# 70.net
KiCad netlist of a schematic drawn in Altium Designer
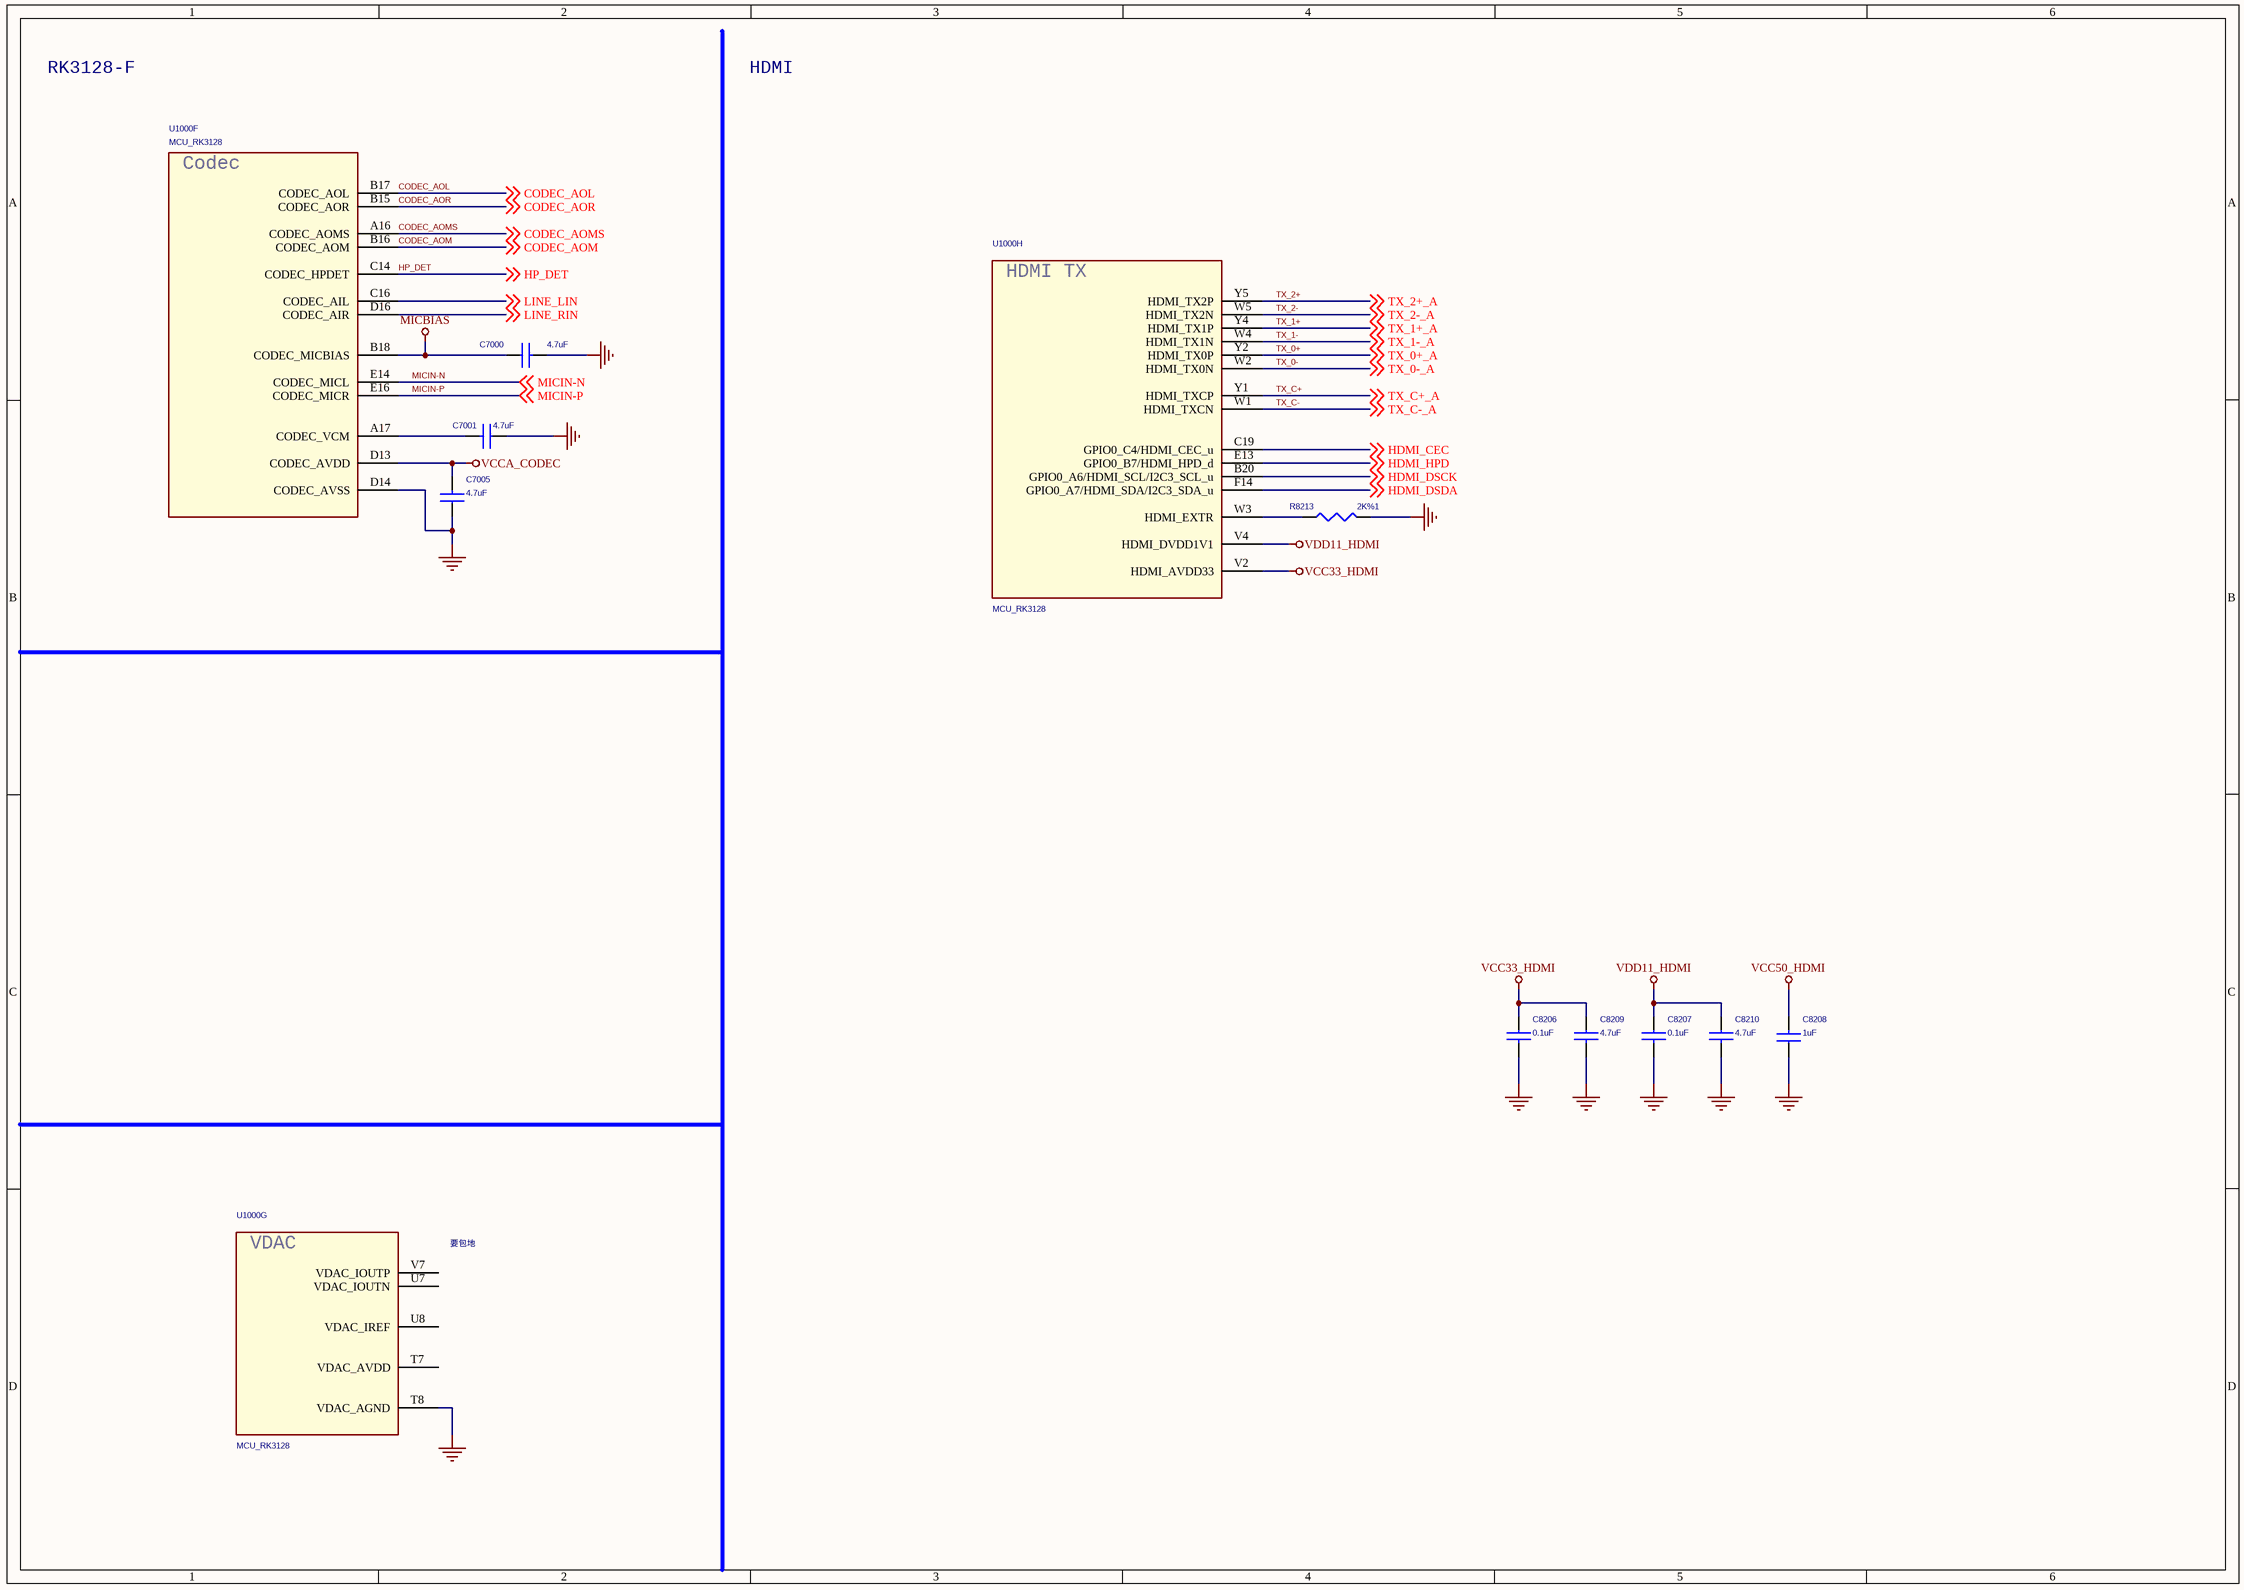
[diagram p0: 70.SchDoc]

(export (version "E")
  (design (tool "Eeschema 10.0.6"))
  (components
    (comp (ref "C7000") (value "4.7uF") (footprint "C0402") (libsource (lib "*") (part "CAP NP")))
    (comp (ref "C7001")
      (value "4.7uF")
      (footprint "C0402")
      (description "CAP,MLCC,10uF,+/-10%,X5R,16V,SMD0805")
      (libsource (lib "*") (part "CAP NP"))
    )
    (comp (ref "C7005")
      (value "4.7uF")
      (footprint "C0402")
      (description "RoHS CHIP CAP 0.1uF +10/-10% X7R")
      (libsource (lib "*") (part "CAP NP"))
    )
    (comp (ref "C8206") (value "0.1uF") (footprint "C0402") (libsource (lib "*") (part "CAP NP")))
    (comp (ref "C8207") (value "0.1uF") (footprint "C0402") (libsource (lib "*") (part "CAP NP")))
    (comp (ref "C8208")
      (value "1uF")
      (footprint "C0402")
      (description "RoHS CHIP CAP 1uF +10/-10% X5R")
      (libsource (lib "*") (part "CAP NP"))
    )
    (comp (ref "C8209") (value "4.7uF") (footprint "C0402") (libsource (lib "*") (part "CAP NP")))
    (comp (ref "C8210") (value "4.7uF") (footprint "C0402") (libsource (lib "*") (part "CAP NP")))
    (comp (ref "R8213")
      (value "2K%1")
      (footprint "R0402")
      (description "RES,thick film,3.5KOhm,+/-5%,1/16W,SMD0402")
      (libsource (lib "*") (part "RESISTOR_0"))
    )
    (comp (ref "U1000")
      (value "MCU_RK3128")
      (footprint "BGA316-14X14-0.65")
      (libsource (lib "*") (part "MCU_RK3128"))
    )
  )
  (nets
    (net (code "1") (name "CODEC_AOL") (class "Default")
      (node (ref "U1000") (pin "B17") (pinfunction "CODEC_AOL_B17") (pintype "passive"))
    )
    (net (code "2") (name "CODEC_AOM") (class "Default")
      (node (ref "U1000") (pin "B16") (pinfunction "CODEC_AOM_B16") (pintype "passive"))
    )
    (net (code "3") (name "CODEC_AOMS") (class "Default")
      (node (ref "U1000") (pin "A16") (pinfunction "CODEC_AOMS_A16") (pintype "passive"))
    )
    (net (code "4") (name "CODEC_AOR") (class "Default")
      (node (ref "U1000") (pin "B15") (pinfunction "CODEC_AOR_B15") (pintype "passive"))
    )
    (net (code "5") (name "GND") (class "Default")
      (node (ref "C7000") (pin "2") (pinfunction "2_2") (pintype "passive"))
      (node (ref "C7001") (pin "1") (pinfunction "1_1") (pintype "passive"))
      (node (ref "C7005") (pin "1") (pinfunction "1_1") (pintype "passive"))
      (node (ref "C8206") (pin "2") (pinfunction "2_2") (pintype "passive"))
      (node (ref "C8207") (pin "2") (pinfunction "2_2") (pintype "passive"))
      (node (ref "C8208") (pin "1") (pinfunction "1_1") (pintype "passive"))
      (node (ref "C8209") (pin "2") (pinfunction "2_2") (pintype "passive"))
      (node (ref "C8210") (pin "2") (pinfunction "2_2") (pintype "passive"))
      (node (ref "R8213") (pin "1") (pinfunction "1_1") (pintype "passive"))
      (node (ref "U1000") (pin "D14") (pinfunction "CODEC_AVSS_D14") (pintype "passive"))
      (node (ref "U1000") (pin "T8") (pinfunction "VDAC_AGND_T8") (pintype "passive"))
    )
    (net (code "6") (name "HDMI_CEC") (class "Default")
      (node (ref "U1000") (pin "C19") (pinfunction "GPIO0_C4/HDMI_CEC_u_C19") (pintype "passive"))
    )
    (net (code "7") (name "HDMI_DSCK") (class "Default")
      (node (ref "U1000") (pin "B20") (pinfunction "GPIO0_A6/HDMI_SCL/I2C3_SCL_u_B20") (pintype "passive"))
    )
    (net (code "8") (name "HDMI_DSDA") (class "Default")
      (node (ref "U1000") (pin "F14") (pinfunction "GPIO0_A7/HDMI_SDA/I2C3_SDA_u_F14") (pintype "passive"))
    )
    (net (code "9") (name "HDMI_HPD") (class "Default")
      (node (ref "U1000") (pin "E13") (pinfunction "GPIO0_B7/HDMI_HPD_d_E13") (pintype "passive"))
    )
    (net (code "10") (name "HP_DET") (class "Default")
      (node (ref "U1000") (pin "C14") (pinfunction "CODEC_HPDET_C14") (pintype "passive"))
    )
    (net (code "11") (name "LINE_LIN") (class "Default")
      (node (ref "U1000") (pin "C16") (pinfunction "CODEC_AIL_C16") (pintype "passive"))
    )
    (net (code "12") (name "LINE_RIN") (class "Default")
      (node (ref "U1000") (pin "D16") (pinfunction "CODEC_AIR_D16") (pintype "passive"))
    )
    (net (code "13") (name "MICBIAS") (class "Default")
      (node (ref "C7000") (pin "1") (pinfunction "1_1") (pintype "passive"))
      (node (ref "U1000") (pin "B18") (pinfunction "CODEC_MICBIAS_B18") (pintype "passive"))
    )
    (net (code "14") (name "MICIN-N") (class "Default")
      (node (ref "U1000") (pin "E14") (pinfunction "CODEC_MICL_E14") (pintype "passive"))
    )
    (net (code "15") (name "MICIN-P") (class "Default")
      (node (ref "U1000") (pin "E16") (pinfunction "CODEC_MICR_E16") (pintype "passive"))
    )
    (net (code "16") (name "Net-(U1000F-CODEC_VCM)") (class "Default")
      (node (ref "C7001") (pin "2") (pinfunction "2_2") (pintype "passive"))
      (node (ref "U1000") (pin "A17") (pinfunction "CODEC_VCM_A17") (pintype "passive"))
    )
    (net (code "17") (name "Net-(U1000H-HDMI_EXTR)") (class "Default")
      (node (ref "R8213") (pin "2") (pinfunction "2_2") (pintype "passive"))
      (node (ref "U1000") (pin "W3") (pinfunction "HDMI_EXTR_W3") (pintype "passive"))
    )
    (net (code "18") (name "TX_0+_A") (class "Default")
      (node (ref "U1000") (pin "Y2") (pinfunction "HDMI_TX0P_Y2") (pintype "passive"))
    )
    (net (code "19") (name "TX_0-_A") (class "Default")
      (node (ref "U1000") (pin "W2") (pinfunction "HDMI_TX0N_W2") (pintype "passive"))
    )
    (net (code "20") (name "TX_1+_A") (class "Default")
      (node (ref "U1000") (pin "Y4") (pinfunction "HDMI_TX1P_Y4") (pintype "passive"))
    )
    (net (code "21") (name "TX_1-_A") (class "Default")
      (node (ref "U1000") (pin "W4") (pinfunction "HDMI_TX1N_W4") (pintype "passive"))
    )
    (net (code "22") (name "TX_2+_A") (class "Default")
      (node (ref "U1000") (pin "Y5") (pinfunction "HDMI_TX2P_Y5") (pintype "passive"))
    )
    (net (code "23") (name "TX_2-_A") (class "Default")
      (node (ref "U1000") (pin "W5") (pinfunction "HDMI_TX2N_W5") (pintype "passive"))
    )
    (net (code "24") (name "TX_C+_A") (class "Default")
      (node (ref "U1000") (pin "Y1") (pinfunction "HDMI_TXCP_Y1") (pintype "passive"))
    )
    (net (code "25") (name "TX_C-_A") (class "Default")
      (node (ref "U1000") (pin "W1") (pinfunction "HDMI_TXCN_W1") (pintype "passive"))
    )
    (net (code "26") (name "VCC33_HDMI") (class "Default")
      (node (ref "C8206") (pin "1") (pinfunction "1_1") (pintype "passive"))
      (node (ref "C8209") (pin "1") (pinfunction "1_1") (pintype "passive"))
      (node (ref "U1000") (pin "V2") (pinfunction "HDMI_AVDD33_V2") (pintype "passive"))
    )
    (net (code "27") (name "VCC50_HDMI") (class "Default")
      (node (ref "C8208") (pin "2") (pinfunction "2_2") (pintype "passive"))
    )
    (net (code "28") (name "VCCA_CODEC") (class "Default")
      (node (ref "C7005") (pin "2") (pinfunction "2_2") (pintype "passive"))
      (node (ref "U1000") (pin "D13") (pinfunction "CODEC_AVDD_D13") (pintype "passive"))
    )
    (net (code "29") (name "VDD11_HDMI") (class "Default")
      (node (ref "C8207") (pin "1") (pinfunction "1_1") (pintype "passive"))
      (node (ref "C8210") (pin "1") (pinfunction "1_1") (pintype "passive"))
      (node (ref "U1000") (pin "V4") (pinfunction "HDMI_DVDD1V1_V4") (pintype "passive"))
    )
    (net (code "30") (name "unconnected-(U1000G-VDAC_AVDD-PadT7)") (class "Default")
      (node (ref "U1000") (pin "T7") (pinfunction "VDAC_AVDD_T7") (pintype "passive"))
    )
    (net (code "31") (name "unconnected-(U1000G-VDAC_IOUTN-PadU7)") (class "Default")
      (node (ref "U1000") (pin "U7") (pinfunction "VDAC_IOUTN_U7") (pintype "passive"))
    )
    (net (code "32") (name "unconnected-(U1000G-VDAC_IOUTP-PadV7)") (class "Default")
      (node (ref "U1000") (pin "V7") (pinfunction "VDAC_IOUTP_V7") (pintype "passive"))
    )
    (net (code "33") (name "unconnected-(U1000G-VDAC_IREF-PadU8)") (class "Default")
      (node (ref "U1000") (pin "U8") (pinfunction "VDAC_IREF_U8") (pintype "passive"))
    )
  )
)
